# Video_out.net
KiCad netlist of a schematic drawn in Altium Designer
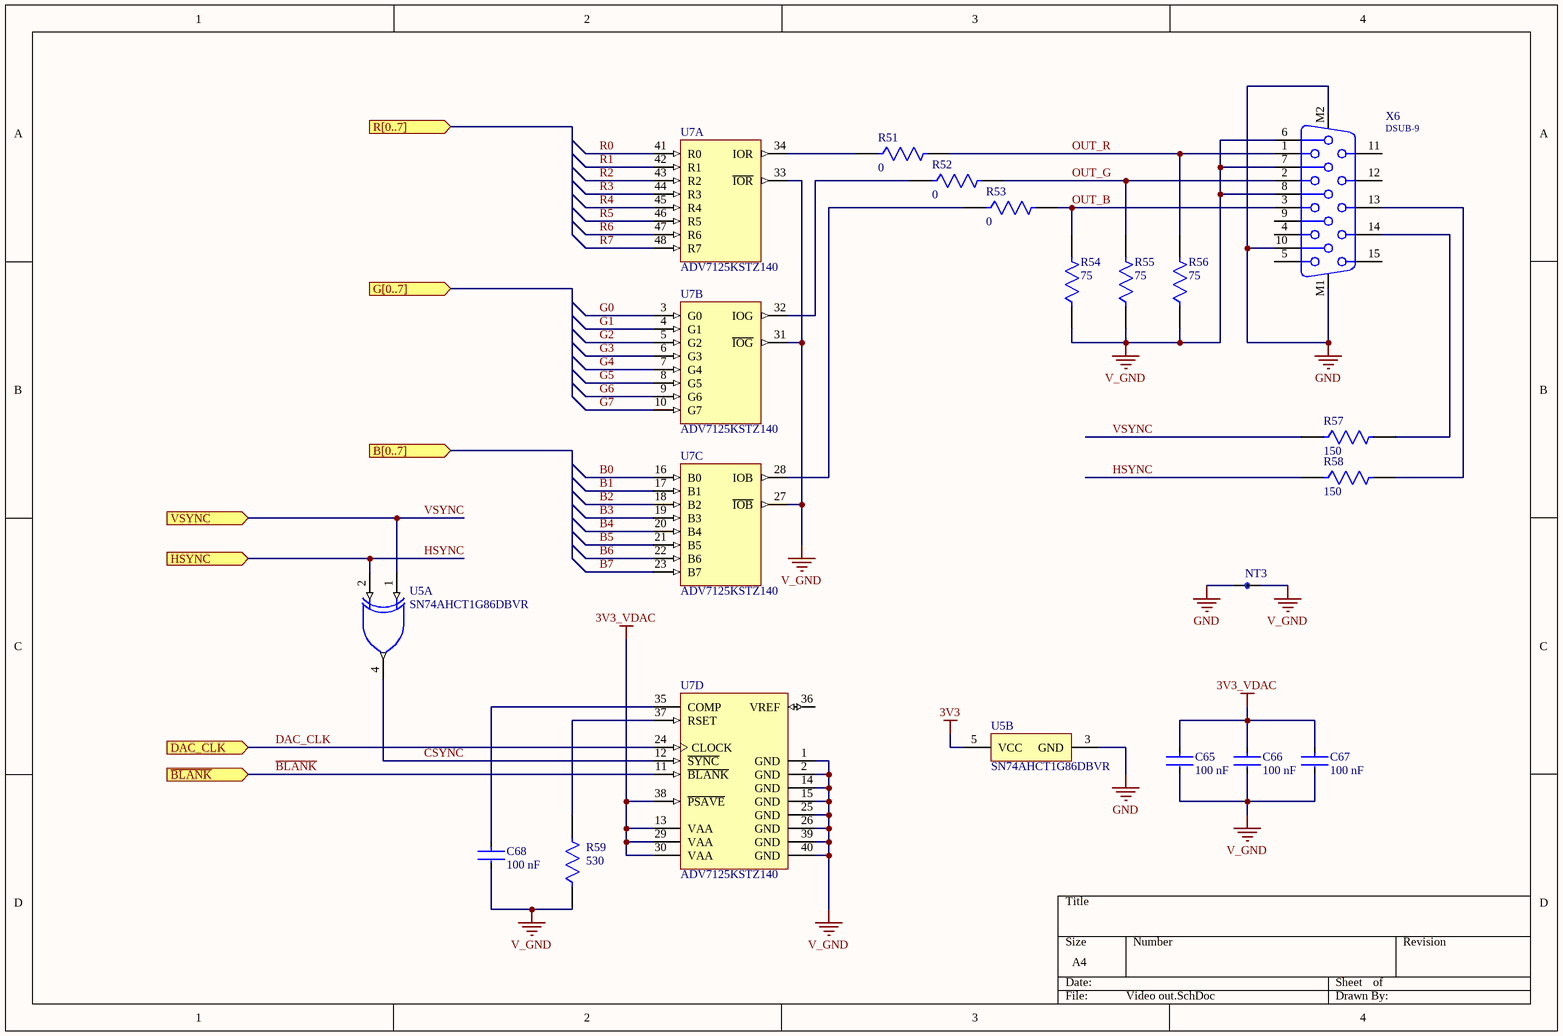
[diagram p0: Video out.SchDoc]

(export (version "E")
  (design (tool "Eeschema 10.0.6"))
  (components
    (comp (ref "C65")
      (value "CC0805-1.5pF")
      (footprint "CC0805")
      (description "CL21 Series 0805 1.5pF 50V ±0.25pF Tolerance C0G Multilayer Ceramic Chip Capacitor")
      (fields
        (field (name "MANUFACTURER PART NUMBER") "CL21C1R5CBANNNC")
        (field (name "CAPACITANCE") "100 nF")
        (field (name "MANUFACTURER") "Samsung")
      )
      (libsource (lib "zxevo") (part "CC0805"))
    )
    (comp (ref "C66")
      (value "CC0805-1.5pF")
      (footprint "CC0805")
      (description "CL21 Series 0805 1.5pF 50V ±0.25pF Tolerance C0G Multilayer Ceramic Chip Capacitor")
      (fields
        (field (name "MANUFACTURER PART NUMBER") "CL21C1R5CBANNNC")
        (field (name "CAPACITANCE") "100 nF")
        (field (name "MANUFACTURER") "Samsung")
      )
      (libsource (lib "zxevo") (part "CC0805"))
    )
    (comp (ref "C67")
      (value "CC0805-1.5pF")
      (footprint "CC0805")
      (description "CL21 Series 0805 1.5pF 50V ±0.25pF Tolerance C0G Multilayer Ceramic Chip Capacitor")
      (fields
        (field (name "MANUFACTURER PART NUMBER") "CL21C1R5CBANNNC")
        (field (name "CAPACITANCE") "100 nF")
        (field (name "MANUFACTURER") "Samsung")
      )
      (libsource (lib "zxevo") (part "CC0805"))
    )
    (comp (ref "C68")
      (value "CC0805-1.5pF")
      (footprint "CC0805")
      (description "CL21 Series 0805 1.5pF 50V ±0.25pF Tolerance C0G Multilayer Ceramic Chip Capacitor")
      (fields
        (field (name "MANUFACTURER PART NUMBER") "CL21C1R5CBANNNC")
        (field (name "CAPACITANCE") "100 nF")
        (field (name "MANUFACTURER") "Samsung")
      )
      (libsource (lib "zxevo") (part "CC0805"))
    )
    (comp (ref "NT3") (value "net_tie") (footprint "NET_TIE") (libsource (lib "zxevo") (part "net_tie")))
    (comp (ref "R51")
      (value "CR0805-51")
      (footprint "CR0805")
      (description "51Ω ±0.5% 0.1W 1/10W Chip Resistor 0805 (2012 Metric) Thin Film")
      (fields
        (field (name "RESISTANCE") "0")
        (field (name "MANUFACTURER") "Susumu")
        (field (name "MANUFACTURER PART NUMBER") "RR1220Q-510-D")
      )
      (libsource (lib "zxevo") (part "CR0805"))
    )
    (comp (ref "R52")
      (value "CR0805-51")
      (footprint "CR0805")
      (description "51Ω ±0.5% 0.1W 1/10W Chip Resistor 0805 (2012 Metric) Thin Film")
      (fields
        (field (name "RESISTANCE") "0")
        (field (name "MANUFACTURER") "Susumu")
        (field (name "MANUFACTURER PART NUMBER") "RR1220Q-510-D")
      )
      (libsource (lib "zxevo") (part "CR0805"))
    )
    (comp (ref "R53")
      (value "CR0805-51")
      (footprint "CR0805")
      (description "51Ω ±0.5% 0.1W 1/10W Chip Resistor 0805 (2012 Metric) Thin Film")
      (fields
        (field (name "RESISTANCE") "0")
        (field (name "MANUFACTURER") "Susumu")
        (field (name "MANUFACTURER PART NUMBER") "RR1220Q-510-D")
      )
      (libsource (lib "zxevo") (part "CR0805"))
    )
    (comp (ref "R54")
      (value "CR0805-51")
      (footprint "CR0805")
      (description "51Ω ±0.5% 0.1W 1/10W Chip Resistor 0805 (2012 Metric) Thin Film")
      (fields
        (field (name "MANUFACTURER") "Susumu")
        (field (name "RESISTANCE") "75")
        (field (name "MANUFACTURER PART NUMBER") "RR1220Q-510-D")
      )
      (libsource (lib "zxevo") (part "CR0805"))
    )
    (comp (ref "R55")
      (value "CR0805-51")
      (footprint "CR0805")
      (description "51Ω ±0.5% 0.1W 1/10W Chip Resistor 0805 (2012 Metric) Thin Film")
      (fields
        (field (name "MANUFACTURER") "Susumu")
        (field (name "RESISTANCE") "75")
        (field (name "MANUFACTURER PART NUMBER") "RR1220Q-510-D")
      )
      (libsource (lib "zxevo") (part "CR0805"))
    )
    (comp (ref "R56")
      (value "CR0805-51")
      (footprint "CR0805")
      (description "51Ω ±0.5% 0.1W 1/10W Chip Resistor 0805 (2012 Metric) Thin Film")
      (fields
        (field (name "MANUFACTURER") "Susumu")
        (field (name "RESISTANCE") "75")
        (field (name "MANUFACTURER PART NUMBER") "RR1220Q-510-D")
      )
      (libsource (lib "zxevo") (part "CR0805"))
    )
    (comp (ref "R57")
      (value "CR0805-51")
      (footprint "CR0805")
      (description "51Ω ±0.5% 0.1W 1/10W Chip Resistor 0805 (2012 Metric) Thin Film")
      (fields
        (field (name "RESISTANCE") "150")
        (field (name "MANUFACTURER") "Susumu")
        (field (name "MANUFACTURER PART NUMBER") "RR1220Q-510-D")
      )
      (libsource (lib "zxevo") (part "CR0805"))
    )
    (comp (ref "R58")
      (value "CR0805-51")
      (footprint "CR0805")
      (description "51Ω ±0.5% 0.1W 1/10W Chip Resistor 0805 (2012 Metric) Thin Film")
      (fields
        (field (name "RESISTANCE") "150")
        (field (name "MANUFACTURER") "Susumu")
        (field (name "MANUFACTURER PART NUMBER") "RR1220Q-510-D")
      )
      (libsource (lib "zxevo") (part "CR0805"))
    )
    (comp (ref "R59")
      (value "CR0805-51")
      (footprint "CR0805")
      (description "51Ω ±0.5% 0.1W 1/10W Chip Resistor 0805 (2012 Metric) Thin Film")
      (fields
        (field (name "RESISTANCE") "530")
        (field (name "MANUFACTURER") "Susumu")
        (field (name "MANUFACTURER PART NUMBER") "RR1220Q-510-D")
      )
      (libsource (lib "zxevo") (part "CR0805"))
    )
    (comp (ref "U5")
      (value "SN74AHCT1G86DBVR")
      (footprint "DBV0005A_L")
      (description "Single 2-Input Exclusive-OR Gate, DBV0005A, LARGE T&R")
      (fields
        (field (name "GENERIC PART NUMBER") "SN74AHCT1G86")
        (field (name "MANUFACTURER") "Texas Instruments")
      )
      (libsource (lib "Altium Content Vault") (part "TI-XOR-1-2IN-5"))
    )
    (comp (ref "U7")
      (value "ADV7125KSTZ140")
      (footprint "ST-48_N")
      (fields (field (name "MANUFACTURER") "Analog Devices"))
      (libsource (lib "zxevo") (part "ADV7125KSTZ140"))
    )
    (comp (ref "X6")
      (value "DSUB-9")
      (footprint "618015330923")
      (description "Female High Density PCB Connector with Hex Screw WR-DSUB, Angled, 15 pins")
      (fields
        (field (name "MANUFACTURER") "Wurth Electronics")
        (field (name "MANUFACTURER PART NUMBER") "618015330923")
      )
      (libsource (lib "zxevo") (part "DSUB-9"))
    )
  )
  (nets
    (net (code "1") (name "/B0") (class "Default")
      (node (ref "U7") (pin "16") (pinfunction "B0_16") (pintype "input"))
    )
    (net (code "2") (name "/B1") (class "Default")
      (node (ref "U7") (pin "17") (pinfunction "B1_17") (pintype "input"))
    )
    (net (code "3") (name "/B2") (class "Default")
      (node (ref "U7") (pin "18") (pinfunction "B2_18") (pintype "input"))
    )
    (net (code "4") (name "/B3") (class "Default")
      (node (ref "U7") (pin "19") (pinfunction "B3_19") (pintype "input"))
    )
    (net (code "5") (name "/B4") (class "Default")
      (node (ref "U7") (pin "20") (pinfunction "B4_20") (pintype "input"))
    )
    (net (code "6") (name "/B5") (class "Default")
      (node (ref "U7") (pin "21") (pinfunction "B5_21") (pintype "input"))
    )
    (net (code "7") (name "/B6") (class "Default")
      (node (ref "U7") (pin "22") (pinfunction "B6_22") (pintype "input"))
    )
    (net (code "8") (name "/B7") (class "Default")
      (node (ref "U7") (pin "23") (pinfunction "B7_23") (pintype "input"))
    )
    (net (code "10") (name "/DAC_CLK") (class "Default")
      (node (ref "U7") (pin "24") (pinfunction "CLOCK_24") (pintype "input"))
    )
    (net (code "11") (name "/G0") (class "Default")
      (node (ref "U7") (pin "3") (pinfunction "G0_3") (pintype "input"))
    )
    (net (code "12") (name "/G1") (class "Default")
      (node (ref "U7") (pin "4") (pinfunction "G1_4") (pintype "input"))
    )
    (net (code "13") (name "/G2") (class "Default")
      (node (ref "U7") (pin "5") (pinfunction "G2_5") (pintype "input"))
    )
    (net (code "14") (name "/G3") (class "Default")
      (node (ref "U7") (pin "6") (pinfunction "G3_6") (pintype "input"))
    )
    (net (code "15") (name "/G4") (class "Default")
      (node (ref "U7") (pin "7") (pinfunction "G4_7") (pintype "input"))
    )
    (net (code "16") (name "/G5") (class "Default")
      (node (ref "U7") (pin "8") (pinfunction "G5_8") (pintype "input"))
    )
    (net (code "17") (name "/G6") (class "Default")
      (node (ref "U7") (pin "9") (pinfunction "G6_9") (pintype "input"))
    )
    (net (code "18") (name "/G7") (class "Default")
      (node (ref "U7") (pin "10") (pinfunction "G7_10") (pintype "input"))
    )
    (net (code "20") (name "/HSYNC") (class "Default")
      (node (ref "R58") (pin "1") (pinfunction "1_1") (pintype "passive"))
      (node (ref "U5") (pin "2") (pinfunction "B_2") (pintype "input"))
    )
    (net (code "21") (name "/OUT_B") (class "Default")
      (node (ref "R53") (pin "2") (pinfunction "2_2") (pintype "passive"))
      (node (ref "R54") (pin "2") (pinfunction "2_2") (pintype "passive"))
      (node (ref "X6") (pin "3") (pinfunction "3_3") (pintype "passive"))
    )
    (net (code "22") (name "/OUT_G") (class "Default")
      (node (ref "R52") (pin "2") (pinfunction "2_2") (pintype "passive"))
      (node (ref "R55") (pin "2") (pinfunction "2_2") (pintype "passive"))
      (node (ref "X6") (pin "2") (pinfunction "2_2") (pintype "passive"))
    )
    (net (code "23") (name "/OUT_R") (class "Default")
      (node (ref "R51") (pin "2") (pinfunction "2_2") (pintype "passive"))
      (node (ref "R56") (pin "2") (pinfunction "2_2") (pintype "passive"))
      (node (ref "X6") (pin "1") (pinfunction "1_1") (pintype "passive"))
    )
    (net (code "24") (name "/R0") (class "Default")
      (node (ref "U7") (pin "41") (pinfunction "R0_41") (pintype "input"))
    )
    (net (code "25") (name "/R1") (class "Default")
      (node (ref "U7") (pin "42") (pinfunction "R1_42") (pintype "input"))
    )
    (net (code "26") (name "/R2") (class "Default")
      (node (ref "U7") (pin "43") (pinfunction "R2_43") (pintype "input"))
    )
    (net (code "27") (name "/R3") (class "Default")
      (node (ref "U7") (pin "44") (pinfunction "R3_44") (pintype "input"))
    )
    (net (code "28") (name "/R4") (class "Default")
      (node (ref "U7") (pin "45") (pinfunction "R4_45") (pintype "input"))
    )
    (net (code "29") (name "/R5") (class "Default")
      (node (ref "U7") (pin "46") (pinfunction "R5_46") (pintype "input"))
    )
    (net (code "30") (name "/R6") (class "Default")
      (node (ref "U7") (pin "47") (pinfunction "R6_47") (pintype "input"))
    )
    (net (code "31") (name "/R7") (class "Default")
      (node (ref "U7") (pin "48") (pinfunction "R7_48") (pintype "input"))
    )
    (net (code "33") (name "/VSYNC") (class "Default")
      (node (ref "R57") (pin "1") (pinfunction "1_1") (pintype "passive"))
      (node (ref "U5") (pin "1") (pinfunction "A_1") (pintype "input"))
    )
    (net (code "34") (name "/~{BLANK}") (class "Default")
      (node (ref "U7") (pin "11") (pinfunction "~{BLANK}_11") (pintype "input"))
    )
    (net (code "35") (name "/~{CSYNC}") (class "Default")
      (node (ref "U5") (pin "4") (pinfunction "Y_4") (pintype "output"))
      (node (ref "U7") (pin "12") (pinfunction "~{SYNC}_12") (pintype "input"))
    )
    (net (code "36") (name "3V3") (class "Default")
      (node (ref "U5") (pin "5") (pinfunction "VCC_5") (pintype "power_in"))
    )
    (net (code "37") (name "3V3_VDAC") (class "Default")
      (node (ref "C65") (pin "1") (pinfunction "1_1") (pintype "passive"))
      (node (ref "C66") (pin "1") (pinfunction "1_1") (pintype "passive"))
      (node (ref "C67") (pin "1") (pinfunction "1_1") (pintype "passive"))
      (node (ref "U7") (pin "13") (pinfunction "VAA_13") (pintype "power_in"))
      (node (ref "U7") (pin "29") (pinfunction "VAA_29") (pintype "power_in"))
      (node (ref "U7") (pin "30") (pinfunction "VAA_30") (pintype "power_in"))
      (node (ref "U7") (pin "38") (pinfunction "~{PSAVE}_38") (pintype "input"))
    )
    (net (code "38") (name "GND") (class "Default")
      (node (ref "NT3") (pin "1") (pintype "passive"))
      (node (ref "U5") (pin "3") (pinfunction "GND_3") (pintype "power_in"))
      (node (ref "X6") (pin "10") (pinfunction "10_10") (pintype "passive"))
      (node (ref "X6") (pin "M1") (pinfunction "M1_M1") (pintype "passive"))
      (node (ref "X6") (pin "M2") (pinfunction "M2_M2") (pintype "passive"))
    )
    (net (code "39") (name "Net-(R57-Pad2)") (class "Default")
      (node (ref "R57") (pin "2") (pinfunction "2_2") (pintype "passive"))
      (node (ref "X6") (pin "14") (pinfunction "14_14") (pintype "passive"))
    )
    (net (code "40") (name "Net-(R58-Pad2)") (class "Default")
      (node (ref "R58") (pin "2") (pinfunction "2_2") (pintype "passive"))
      (node (ref "X6") (pin "13") (pinfunction "13_13") (pintype "passive"))
    )
    (net (code "41") (name "Net-(U7A-IOR)") (class "Default")
      (node (ref "R51") (pin "1") (pinfunction "1_1") (pintype "passive"))
      (node (ref "U7") (pin "34") (pinfunction "IOR_34") (pintype "output"))
    )
    (net (code "42") (name "Net-(U7B-IOG)") (class "Default")
      (node (ref "R52") (pin "1") (pinfunction "1_1") (pintype "passive"))
      (node (ref "U7") (pin "32") (pinfunction "IOG_32") (pintype "output"))
    )
    (net (code "43") (name "Net-(U7C-IOB)") (class "Default")
      (node (ref "R53") (pin "1") (pinfunction "1_1") (pintype "passive"))
      (node (ref "U7") (pin "28") (pinfunction "IOB_28") (pintype "output"))
    )
    (net (code "44") (name "Net-(U7D-COMP)") (class "Default")
      (node (ref "C68") (pin "1") (pinfunction "1_1") (pintype "passive"))
      (node (ref "U7") (pin "35") (pinfunction "COMP_35") (pintype "passive"))
    )
    (net (code "45") (name "Net-(U7D-RSET)") (class "Default")
      (node (ref "R59") (pin "2") (pinfunction "2_2") (pintype "passive"))
      (node (ref "U7") (pin "37") (pinfunction "RSET_37") (pintype "input"))
    )
    (net (code "46") (name "V_GND") (class "Default")
      (node (ref "C65") (pin "2") (pinfunction "2_2") (pintype "passive"))
      (node (ref "C66") (pin "2") (pinfunction "2_2") (pintype "passive"))
      (node (ref "C67") (pin "2") (pinfunction "2_2") (pintype "passive"))
      (node (ref "C68") (pin "2") (pinfunction "2_2") (pintype "passive"))
      (node (ref "NT3") (pin "2") (pintype "passive"))
      (node (ref "R54") (pin "1") (pinfunction "1_1") (pintype "passive"))
      (node (ref "R55") (pin "1") (pinfunction "1_1") (pintype "passive"))
      (node (ref "R56") (pin "1") (pinfunction "1_1") (pintype "passive"))
      (node (ref "R59") (pin "1") (pinfunction "1_1") (pintype "passive"))
      (node (ref "U7") (pin "1") (pinfunction "GND_1") (pintype "power_in"))
      (node (ref "U7") (pin "14") (pinfunction "GND_14") (pintype "power_in"))
      (node (ref "U7") (pin "15") (pinfunction "GND_15") (pintype "power_in"))
      (node (ref "U7") (pin "2") (pinfunction "GND_2") (pintype "power_in"))
      (node (ref "U7") (pin "25") (pinfunction "GND_25") (pintype "power_in"))
      (node (ref "U7") (pin "26") (pinfunction "GND_26") (pintype "power_in"))
      (node (ref "U7") (pin "27") (pinfunction "~{IOB}_27") (pintype "output"))
      (node (ref "U7") (pin "31") (pinfunction "~{IOG}_31") (pintype "output"))
      (node (ref "U7") (pin "33") (pinfunction "~{IOR}_33") (pintype "output"))
      (node (ref "U7") (pin "39") (pinfunction "GND_39") (pintype "power_in"))
      (node (ref "U7") (pin "40") (pinfunction "GND_40") (pintype "power_in"))
      (node (ref "X6") (pin "6") (pinfunction "6_6") (pintype "passive"))
      (node (ref "X6") (pin "7") (pinfunction "7_7") (pintype "passive"))
      (node (ref "X6") (pin "8") (pinfunction "8_8") (pintype "passive"))
    )
    (net (code "47") (name "unconnected-(U7D-VREF-Pad36)") (class "Default")
      (node (ref "U7") (pin "36") (pinfunction "VREF_36") (pintype "bidirectional"))
    )
    (net (code "48") (name "unconnected-(X6-Pad4)") (class "Default")
      (node (ref "X6") (pin "4") (pinfunction "4_4") (pintype "passive"))
    )
    (net (code "49") (name "unconnected-(X6-Pad5)") (class "Default")
      (node (ref "X6") (pin "5") (pinfunction "5_5") (pintype "passive"))
    )
    (net (code "50") (name "unconnected-(X6-Pad9)") (class "Default")
      (node (ref "X6") (pin "9") (pinfunction "9_9") (pintype "passive"))
    )
    (net (code "51") (name "unconnected-(X6-Pad11)") (class "Default")
      (node (ref "X6") (pin "11") (pinfunction "11_11") (pintype "passive"))
    )
    (net (code "52") (name "unconnected-(X6-Pad12)") (class "Default")
      (node (ref "X6") (pin "12") (pinfunction "12_12") (pintype "passive"))
    )
    (net (code "53") (name "unconnected-(X6-Pad15)") (class "Default")
      (node (ref "X6") (pin "15") (pinfunction "15_15") (pintype "passive"))
    )
  )
)
